# 7_1_VA_CP.net
KiCad netlist of a schematic drawn in Altium Designer
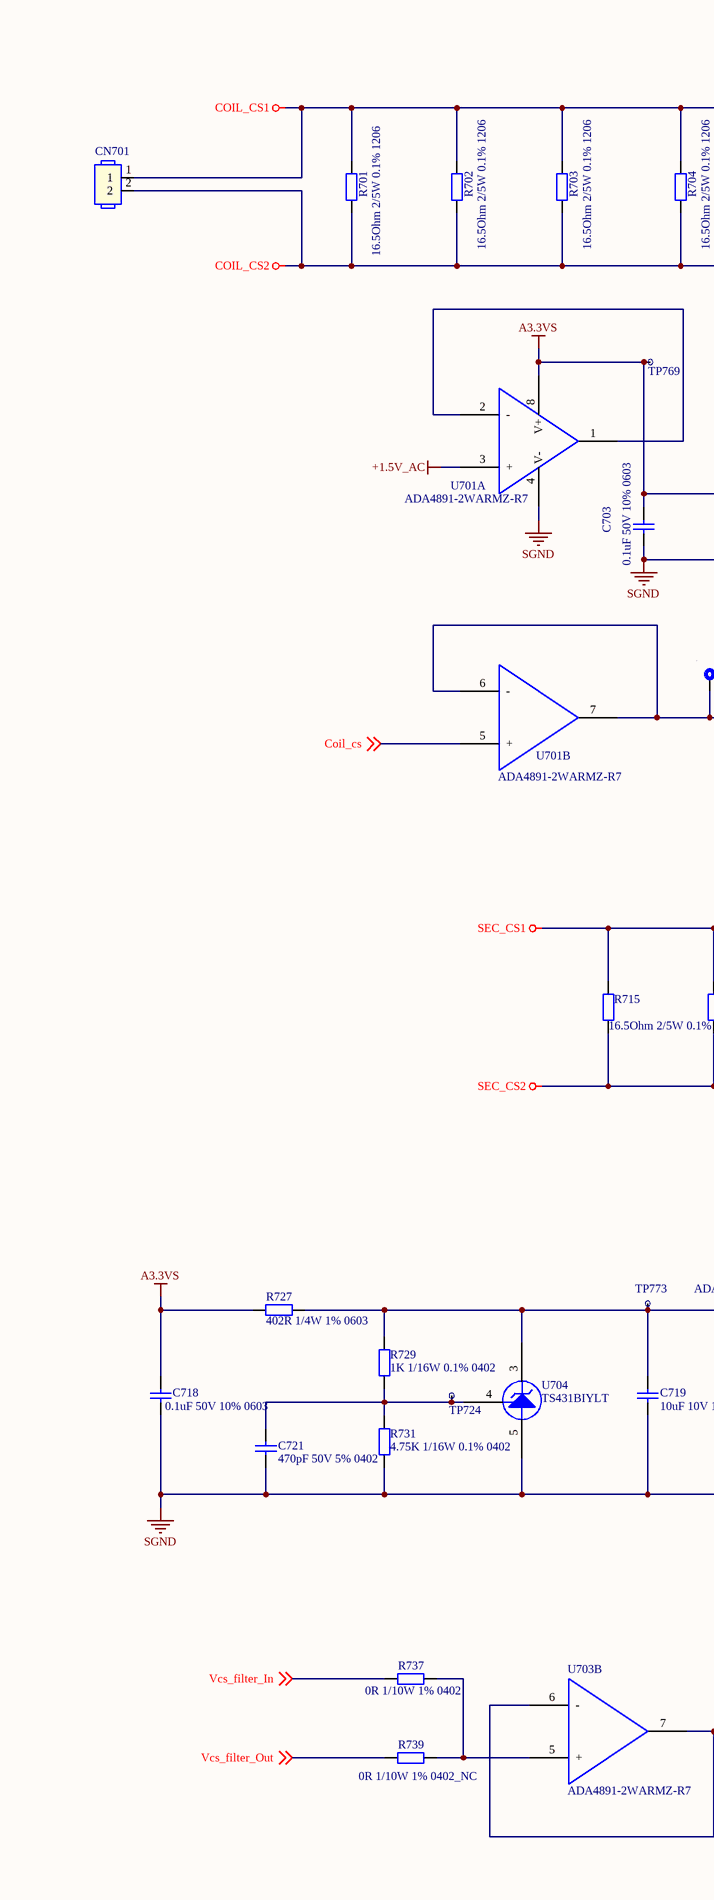
[diagram p0: 7.1 VA_CP.SchDoc, left]
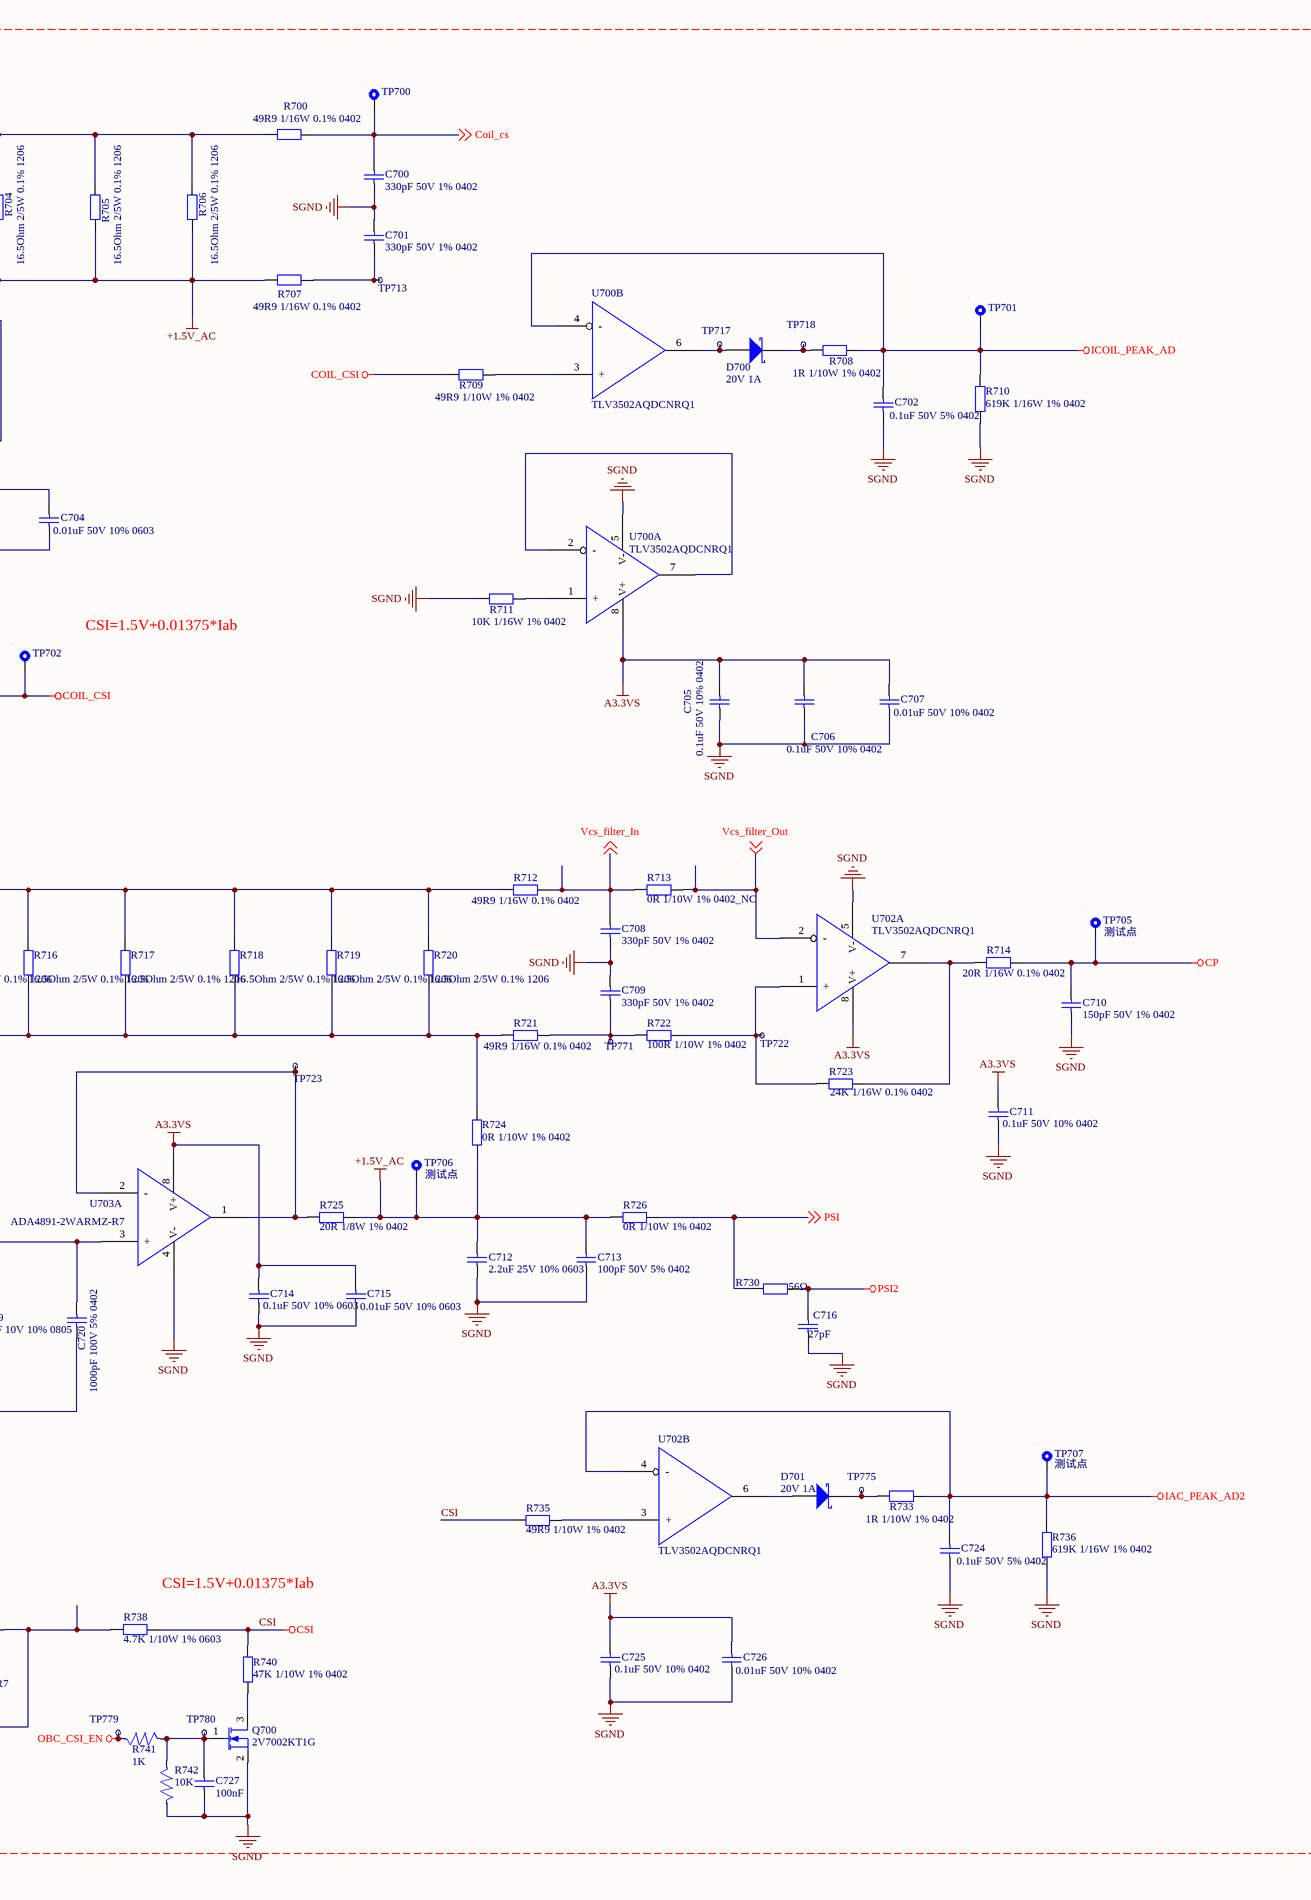
[diagram p1: 7.1 VA_CP.SchDoc, right]

(export (version "E")
  (design (tool "Eeschema 10.0.6"))
  (components
    (comp (ref "C700")
      (value "330pF 50V 1% 0402")
      (footprint "C0402")
      (description "CAP CER 330pF 50V 1% C0G/NP0 0402 AEC-Q200 SMD")
      (libsource (lib "Miscellaneous Devices") (part "Cap Semi"))
    )
    (comp (ref "C701")
      (value "330pF 50V 1% 0402")
      (footprint "C0402")
      (description "CAP CER 330pF 50V 1% C0G/NP0 0402 AEC-Q200 SMD")
      (libsource (lib "Miscellaneous Devices") (part "Cap Semi"))
    )
    (comp (ref "C702")
      (value "0.1uF 50V 5% 0402")
      (footprint "C0402")
      (description "CAP CER 0.1uF 100V 5% C0G/NP0 1206 AEC-Q200 SMD")
      (libsource (lib "Miscellaneous Devices") (part "Cap Semi"))
    )
    (comp (ref "C703")
      (value "0.1uF 50V 10% 0603")
      (footprint "C0603")
      (description "CAP CER 0.1uF 50V 10% X7R 0603 AEC-Q200 SMD")
      (libsource (lib "Miscellaneous Devices") (part "Cap Semi"))
    )
    (comp (ref "C704")
      (value "0.01uF 50V 10% 0603")
      (footprint "C0603")
      (description "CAP CER 0.01uF 50V 10% X7R 0603 AEC-Q200 SMD")
      (libsource (lib "Miscellaneous Devices") (part "Cap Semi"))
    )
    (comp (ref "C705")
      (value "0.1uF 50V 10% 0402")
      (footprint "C0402")
      (description "CAP CER 0.1uF 50V 10% X7R 0603 AEC-Q200 SMD")
      (libsource (lib "Miscellaneous Devices") (part "Cap Semi"))
    )
    (comp (ref "C706")
      (value "0.1uF 50V 10% 0402")
      (footprint "C0402")
      (description "CAP CER 0.1uF 50V 10% X7R 0603 AEC-Q200 SMD")
      (libsource (lib "Miscellaneous Devices") (part "Cap Semi"))
    )
    (comp (ref "C707")
      (value "0.01uF 50V 10% 0402")
      (footprint "C0402")
      (description "CAP CER 0.01uF 50V 10% X7R 0603 AEC-Q200 SMD")
      (libsource (lib "Miscellaneous Devices") (part "Cap Semi"))
    )
    (comp (ref "C708")
      (value "330pF 50V 1% 0402")
      (footprint "C0402")
      (description "CAP CER 330pF 50V 1% C0G/NP0 0402 AEC-Q200 SMD")
      (libsource (lib "Miscellaneous Devices") (part "Cap Semi"))
    )
    (comp (ref "C709")
      (value "330pF 50V 1% 0402")
      (footprint "C0402")
      (description "CAP CER 330pF 50V 1% C0G/NP0 0402 AEC-Q200 SMD")
      (libsource (lib "Miscellaneous Devices") (part "Cap Semi"))
    )
    (comp (ref "C710")
      (value "150pF 50V 1% 0402")
      (footprint "C0402")
      (description "CAP CER 150pF 50V 1% C0G/NP0 AEC-Q200 0402 SMD")
      (libsource (lib "Miscellaneous Devices") (part "Cap Semi"))
    )
    (comp (ref "C711")
      (value "0.1uF 50V 10% 0402")
      (footprint "C0402")
      (description "CAP CER 0.1uF 50V 10% X7R 0603 AEC-Q200 SMD")
      (libsource (lib "Miscellaneous Devices") (part "Cap Semi"))
    )
    (comp (ref "C712")
      (value "2.2uF 25V 10% 0603")
      (footprint "C0603")
      (description "CAP CER 2.2uF 25V 10% X5R 0603 SMD")
      (libsource (lib "Miscellaneous Devices") (part "Cap Semi"))
    )
    (comp (ref "C713")
      (value "100pF 50V 5% 0402")
      (footprint "C0402")
      (description "CAP CER 100pF 50V 5% C0G/NP0 0603 SMD")
      (libsource (lib "Miscellaneous Devices") (part "Cap Semi"))
    )
    (comp (ref "C714")
      (value "0.1uF 50V 10% 0603")
      (footprint "C0402")
      (description "CAP CER 0.1uF 50V 10% X7R 0603 AEC-Q200 SMD")
      (libsource (lib "Miscellaneous Devices") (part "Cap Semi"))
    )
    (comp (ref "C715")
      (value "0.01uF 50V 10% 0603")
      (footprint "C0402")
      (description "CAP CER 0.01uF 50V 10% X7R 0603 AEC-Q200 SMD")
      (libsource (lib "Miscellaneous Devices") (part "Cap Semi"))
    )
    (comp (ref "C716")
      (value "27pF 50V±5% C0G  0402")
      (footprint "C0402")
      (fields (field (name "值") "27pF"))
      (libsource (lib "贴片电容原理图封装库") (part "27pF 50V±5% C0G  0402"))
    )
    (comp (ref "C718")
      (value "0.1uF 50V 10% 0603")
      (footprint "C0603")
      (description "CAP CER 0.1uF 50V 10% X7R 0603 AEC-Q200 SMD")
      (libsource (lib "Miscellaneous Devices") (part "Cap Semi"))
    )
    (comp (ref "C719")
      (value "10uF 10V 10% 0805")
      (footprint "C0805")
      (description "CAP CER 10uF 35V 10% X5R 0805 SMD")
      (libsource (lib "Miscellaneous Devices") (part "Cap Semi"))
    )
    (comp (ref "C720")
      (value "1000pF 100V 5% 0402")
      (footprint "C0402")
      (description "CAP CER 1000pF 100V 5% X7R 0402 AEC-Q200 SMD")
      (libsource (lib "Miscellaneous Devices") (part "Cap Semi"))
    )
    (comp (ref "C721")
      (value "470pF 50V 5% 0402")
      (footprint "C0402")
      (description "CAP CER 470pF 50V 5% C0G/NP0 0402 AEC-Q200 SMD")
      (libsource (lib "Miscellaneous Devices") (part "Cap Semi"))
    )
    (comp (ref "C724")
      (value "0.1uF 50V 5% 0402")
      (footprint "C0402")
      (description "CAP CER 0.1uF 100V 5% C0G/NP0 1206 AEC-Q200 SMD")
      (libsource (lib "Miscellaneous Devices") (part "Cap Semi"))
    )
    (comp (ref "C725")
      (value "0.1uF 50V 10% 0402")
      (footprint "C0402")
      (description "CAP CER 0.1uF 50V 10% X7R 0603 AEC-Q200 SMD")
      (libsource (lib "Miscellaneous Devices") (part "Cap Semi"))
    )
    (comp (ref "C726")
      (value "0.01uF 50V 10% 0402")
      (footprint "C0402")
      (description "CAP CER 0.01uF 50V 10% X7R 0603 AEC-Q200 SMD")
      (libsource (lib "Miscellaneous Devices") (part "Cap Semi"))
    )
    (comp (ref "C727")
      (value "100nF")
      (footprint "C0402")
      (fields (field (name "MANUFACTURER") "Yageo"))
      (libsource (lib "*") (part "Cap"))
    )
    (comp (ref "CN701")
      (value "~")
      (footprint "HY_2MM_1*2P_90MOLEX01")
      (description "CN1.25-02P")
      (libsource (lib "原理图符号库2.0") (part "CN1.25-02P"))
    )
    (comp (ref "D700")
      (value "20V 1A")
      (footprint "SOD-882D")
      (description "DIODE SBD 20V 1A SOD-882D AEC-Q101")
      (libsource (lib "Miscellaneous Devices") (part "D Schottky"))
    )
    (comp (ref "D701")
      (value "20V 1A")
      (footprint "SOD-882D")
      (description "DIODE SBD 20V 1A SOD-882D AEC-Q101")
      (libsource (lib "Miscellaneous Devices") (part "D Schottky"))
    )
    (comp (ref "Q700")
      (value "2V7002KT1G")
      (footprint "Q_SOT23 - 2")
      (fields (field (name "MANUFACTURER") "ONSemi"))
      (libsource (lib "*") (part "MOSFET_N CHANNEL"))
    )
    (comp (ref "R700")
      (value "49R9 1/16W 0.1% 0402")
      (footprint "R0402")
      (description "RES Thin Film 49R9 1/16W 0.1% 0402 AEC-Q200 SMD")
      (libsource (lib "") (part "Res2_2"))
    )
    (comp (ref "R701")
      (value "16.5Ohm 2/5W 0.1% 1206")
      (footprint "R1206")
      (description "RES Thin Film 16.5Ohm 2/5W 0.1% 1206 AEC-Q200 SMD")
      (libsource (lib "") (part "Res2_1"))
    )
    (comp (ref "R702")
      (value "16.5Ohm 2/5W 0.1% 1206")
      (footprint "R1206")
      (description "RES Thin Film 16.5Ohm 2/5W 0.1% 1206 AEC-Q200 SMD")
      (libsource (lib "") (part "Res2_1"))
    )
    (comp (ref "R703")
      (value "16.5Ohm 2/5W 0.1% 1206")
      (footprint "R1206")
      (description "RES Thin Film 16.5Ohm 2/5W 0.1% 1206 AEC-Q200 SMD")
      (libsource (lib "") (part "Res2_1"))
    )
    (comp (ref "R704")
      (value "16.5Ohm 2/5W 0.1% 1206")
      (footprint "R1206")
      (description "RES Thin Film 16.5Ohm 2/5W 0.1% 1206 AEC-Q200 SMD")
      (libsource (lib "") (part "Res2_1"))
    )
    (comp (ref "R705")
      (value "16.5Ohm 2/5W 0.1% 1206")
      (footprint "R1206")
      (description "RES Thin Film 16.5Ohm 2/5W 0.1% 1206 AEC-Q200 SMD")
      (libsource (lib "") (part "Res2_1"))
    )
    (comp (ref "R706")
      (value "16.5Ohm 2/5W 0.1% 1206")
      (footprint "R1206")
      (description "RES Thin Film 16.5Ohm 2/5W 0.1% 1206 AEC-Q200 SMD")
      (libsource (lib "") (part "Res2_1"))
    )
    (comp (ref "R707")
      (value "49R9 1/16W 0.1% 0402")
      (footprint "R0402")
      (description "RES Thin Film 49R9 1/16W 0.1% 0402 AEC-Q200 SMD")
      (libsource (lib "") (part "Res2_2"))
    )
    (comp (ref "R708")
      (value "1R 1/10W 1% 0402")
      (footprint "R0402")
      (description "RES Thick Film 1R 1/10W 1% 0603 AEC-Q200 SMD")
      (libsource (lib "") (part "Res2_2"))
    )
    (comp (ref "R709")
      (value "49R9 1/10W 1% 0402")
      (footprint "R0402")
      (description "RES Thick Film 49R9 1/10W 1% 0603 AEC-Q200 SMD")
      (libsource (lib "") (part "Res2_2"))
    )
    (comp (ref "R710")
      (value "619K 1/16W 1% 0402")
      (footprint "R0402")
      (description "RES Thick Film 619K 1/16W 1% 0402 AEC-Q200 SMD")
      (libsource (lib "Miscellaneous Devices") (part "Res2"))
    )
    (comp (ref "R711")
      (value "10K 1/16W 1% 0402")
      (footprint "R0402")
      (description "RES Thick Film 10K 1/16W 1% 0402 SMD")
      (libsource (lib "") (part "Res2_2"))
    )
    (comp (ref "R712")
      (value "49R9 1/16W 0.1% 0402")
      (footprint "R0402")
      (description "RES Thin Film 49R9 1/16W 0.1% 0402 AEC-Q200 SMD")
      (libsource (lib "") (part "Res2_2"))
    )
    (comp (ref "R713")
      (value "0R 1/10W 1% 0402_NC")
      (footprint "R0402")
      (description "RES Thick Film 0R 1/10W 1% 0603 SMD")
      (libsource (lib "") (part "Res2_2"))
    )
    (comp (ref "R714")
      (value "20R 1/16W 0.1% 0402")
      (footprint "R0402")
      (description "RES Thin Film 20R 1/16W 0.1% 0402 AEC-Q200 SMD")
      (libsource (lib "") (part "Res2_2"))
    )
    (comp (ref "R715")
      (value "16.5Ohm 2/5W 0.1% 1206")
      (footprint "R1206")
      (description "RES Thin Film 16.5Ohm 2/5W 0.1% 1206 AEC-Q200 SMD")
      (libsource (lib "") (part "Res2_1"))
    )
    (comp (ref "R716")
      (value "16.5Ohm 2/5W 0.1% 1206")
      (footprint "R1206")
      (description "RES Thin Film 16.5Ohm 2/5W 0.1% 1206 AEC-Q200 SMD")
      (libsource (lib "") (part "Res2_1"))
    )
    (comp (ref "R717")
      (value "16.5Ohm 2/5W 0.1% 1206")
      (footprint "R1206")
      (description "RES Thin Film 16.5Ohm 2/5W 0.1% 1206 AEC-Q200 SMD")
      (libsource (lib "") (part "Res2_1"))
    )
    (comp (ref "R718")
      (value "16.5Ohm 2/5W 0.1% 1206")
      (footprint "R1206")
      (description "RES Thin Film 16.5Ohm 2/5W 0.1% 1206 AEC-Q200 SMD")
      (libsource (lib "") (part "Res2_1"))
    )
    (comp (ref "R719")
      (value "16.5Ohm 2/5W 0.1% 1206")
      (footprint "R1206")
      (description "RES Thin Film 16.5Ohm 2/5W 0.1% 1206 AEC-Q200 SMD")
      (libsource (lib "") (part "Res2_1"))
    )
    (comp (ref "R720")
      (value "16.5Ohm 2/5W 0.1% 1206")
      (footprint "R1206")
      (description "RES Thin Film 16.5Ohm 2/5W 0.1% 1206 AEC-Q200 SMD")
      (libsource (lib "") (part "Res2_1"))
    )
    (comp (ref "R721")
      (value "49R9 1/16W 0.1% 0402")
      (footprint "R0402")
      (description "RES Thin Film 49R9 1/16W 0.1% 0402 AEC-Q200 SMD")
      (libsource (lib "") (part "Res2_2"))
    )
    (comp (ref "R722")
      (value "100R 1/10W 1% 0402")
      (footprint "R0402")
      (description "RES Thick Film 100R 1/10W 1% 0603 AEC-Q200 SMD")
      (libsource (lib "") (part "Res2_2"))
    )
    (comp (ref "R723")
      (value "24K 1/16W 0.1% 0402")
      (footprint "R0402")
      (description "RES Thin Film 24K 1/16W 0.1% 0402 AEC-Q200 SMD")
      (libsource (lib "") (part "Res2_2"))
    )
    (comp (ref "R724")
      (value "0R 1/10W 1% 0402")
      (footprint "R0402")
      (description "RES Thick Film 0R 1/10W 1% AEC-Q200 0603 SMD")
      (libsource (lib "Miscellaneous Devices") (part "Res2"))
    )
    (comp (ref "R725")
      (value "20R 1/8W 1% 0402")
      (footprint "R0402")
      (description "RES Thick Film 20R 1/8W 1% 0805 AEC-Q200 SMD")
      (libsource (lib "") (part "Res2_2"))
    )
    (comp (ref "R726")
      (value "0R 1/10W 1% 0402")
      (footprint "R0402")
      (description "RES Thick Film 0R 1/10W 1% AEC-Q200 0603 SMD")
      (libsource (lib "") (part "Res2_2"))
    )
    (comp (ref "R727")
      (value "402R 1/4W 1% 0603")
      (footprint "R0603")
      (description "RES Thick Film 402R 1/4W 1% 1206 AEC-Q200 SMD")
      (libsource (lib "") (part "Res2_2"))
    )
    (comp (ref "R729")
      (value "1K 1/16W 0.1% 0402")
      (footprint "R0402")
      (description "RES Thin Film 1K 1/16W 0.1% 0402 AEC-Q200 SMD")
      (libsource (lib "") (part "Res2_1"))
    )
    (comp (ref "R730")
      (value "56Ω ±1% 1/16W 0402")
      (footprint "R0402")
      (fields (field (name "值") "56Ω"))
      (libsource (lib "贴片电阻原理图封装库") (part "56Ω ±1% 1/16W 0402"))
    )
    (comp (ref "R731")
      (value "4.75K 1/16W 0.1% 0402")
      (footprint "R0402")
      (description "RES Thin Film 4.75K 1/16W 0.1% 0402 AEC-Q200 SMD")
      (libsource (lib "") (part "Res2_1"))
    )
    (comp (ref "R733")
      (value "1R 1/10W 1% 0402")
      (footprint "R0402")
      (description "RES Thick Film 1R 1/10W 1% 0603 AEC-Q200 SMD")
      (libsource (lib "") (part "Res2_2"))
    )
    (comp (ref "R735")
      (value "49R9 1/10W 1% 0402")
      (footprint "R0402")
      (description "RES Thick Film 49R9 1/10W 1% 0603 AEC-Q200 SMD")
      (libsource (lib "") (part "Res2_2"))
    )
    (comp (ref "R736")
      (value "619K 1/16W 1% 0402")
      (footprint "R0402")
      (description "RES Thick Film 619K 1/16W 1% 0402 AEC-Q200 SMD")
      (libsource (lib "Miscellaneous Devices") (part "Res2"))
    )
    (comp (ref "R737")
      (value "0R 1/10W 1% 0402")
      (footprint "R0402")
      (description "RES Thick Film 0R 1/10W 1% AEC-Q200 0603 SMD")
      (libsource (lib "") (part "Res2_2"))
    )
    (comp (ref "R738")
      (value "4.7K 1/10W 1% 0603")
      (footprint "R0402")
      (description "RES Thick Film 49R9 1/10W 1% 0603 AEC-Q200 SMD")
      (libsource (lib "") (part "Res2_2"))
    )
    (comp (ref "R739")
      (value "0R 1/10W 1% 0402_NC")
      (footprint "R0402")
      (description "RES Thick Film 0R 1/10W 1% AEC-Q200 0603 SMD")
      (libsource (lib "") (part "Res2_2"))
    )
    (comp (ref "R740")
      (value "47K 1/10W 1% 0402")
      (footprint "R0402")
      (description "RES Thick Film 49R9 1/10W 1% 0603 AEC-Q200 SMD")
      (libsource (lib "Miscellaneous Devices") (part "Res2"))
    )
    (comp (ref "R741")
      (value "1K")
      (footprint "R0402")
      (fields (field (name "MANUFACTURER") "Yageo"))
      (libsource (lib "*") (part "RESISTOR_1206"))
    )
    (comp (ref "R742")
      (value "10K")
      (footprint "R0402")
      (fields (field (name "MANUFACTURER") "Yageo"))
      (libsource (lib "*") (part "RESISTOR_1206"))
    )
    (comp (ref "TP700")
      (value "测试点")
      (footprint "测试点")
      (description "Test Point 1mm")
      (libsource (lib "Test Point") (part "Test Point"))
    )
    (comp (ref "TP701")
      (value "测试点")
      (footprint "测试点")
      (description "Test Point 1mm")
      (libsource (lib "Test Point") (part "Test Point"))
    )
    (comp (ref "TP702")
      (value "测试点")
      (footprint "测试点")
      (description "Test Point 1mm")
      (libsource (lib "Test Point") (part "Test Point"))
    )
    (comp (ref "TP705")
      (value "测试点")
      (footprint "测试点")
      (description "Test Point 1mm")
      (libsource (lib "Test Point") (part "Test Point"))
    )
    (comp (ref "TP706")
      (value "测试点")
      (footprint "测试点")
      (description "Test Point 1mm")
      (libsource (lib "Test Point") (part "Test Point"))
    )
    (comp (ref "TP707")
      (value "测试点")
      (footprint "测试点")
      (description "Test Point 1mm")
      (libsource (lib "Test Point") (part "Test Point"))
    )
    (comp (ref "TP713") (value "测试点") (footprint "测试点") (libsource (lib "原理图符号库2.0") (part "测试点")))
    (comp (ref "TP717") (value "测试点") (footprint "测试点") (libsource (lib "原理图符号库2.0") (part "测试点")))
    (comp (ref "TP718") (value "测试点") (footprint "测试点") (libsource (lib "原理图符号库2.0") (part "测试点")))
    (comp (ref "TP722") (value "测试点") (footprint "测试点") (libsource (lib "原理图符号库2.0") (part "测试点")))
    (comp (ref "TP723") (value "测试点") (footprint "测试点") (libsource (lib "原理图符号库2.0") (part "测试点")))
    (comp (ref "TP724") (value "测试点") (footprint "测试点") (libsource (lib "原理图符号库2.0") (part "测试点")))
    (comp (ref "TP769") (value "测试点") (footprint "测试点") (libsource (lib "原理图符号库2.0") (part "测试点")))
    (comp (ref "TP771") (value "测试点") (footprint "测试点") (libsource (lib "原理图符号库2.0") (part "测试点")))
    (comp (ref "TP773") (value "测试点") (footprint "测试点") (libsource (lib "原理图符号库2.0") (part "测试点")))
    (comp (ref "TP775") (value "测试点") (footprint "测试点") (libsource (lib "原理图符号库2.0") (part "测试点")))
    (comp (ref "TP779") (value "测试点") (footprint "测试点") (libsource (lib "原理图符号库2.0") (part "测试点")))
    (comp (ref "TP780") (value "测试点") (footprint "测试点") (libsource (lib "原理图符号库2.0") (part "测试点")))
    (comp (ref "U700")
      (value "TLV3502AQDCNRQ1")
      (footprint "SON-8")
      (description "IC COMPARATOR 2.7V~5.5V SOT23-8")
      (libsource (lib "TLV3502AQDCNRQ1") (part "TLV3502AQDCNRQ1"))
    )
    (comp (ref "U701")
      (value "ADA4891-2WARMZ-R7")
      (footprint "SOIC_8")
      (description "IC, High Speed, Rail-to-Rail Amplifiers, 2.7V~5.5V, MSOP-8")
      (libsource (lib "ADA4891-2WARMZ-R7") (part "ADA4891-2WARMZ-R7"))
    )
    (comp (ref "U702")
      (value "TLV3502AQDCNRQ1")
      (footprint "SON-8")
      (description "IC COMPARATOR 2.7V~5.5V SOT23-8")
      (libsource (lib "TLV3502AQDCNRQ1") (part "TLV3502AQDCNRQ1"))
    )
    (comp (ref "U703")
      (value "ADA4891-2WARMZ-R7")
      (footprint "SOIC_8")
      (description "IC, High Speed, Rail-to-Rail Amplifiers, 2.7V~5.5V, MSOP-8")
      (libsource (lib "ADA4891-2WARMZ-R7") (part "ADA4891-2WARMZ-R7"))
    )
    (comp (ref "U704")
      (value "TS431BIYLT")
      (footprint "SOT23-5")
      (description "IC VREF SHUNT ADJ 1.24V~6V 30mA SOT23-5")
      (libsource (lib "TS431BIYLT") (part "TS431BIYLT"))
    )
  )
  (nets
    (net (code "1") (name "+1.5V_AC") (class "Default")
      (node (ref "C712") (pin "2") (pinfunction "2_2") (pintype "passive"))
      (node (ref "C713") (pin "2") (pinfunction "2_2") (pintype "passive"))
      (node (ref "CN701") (pin "2") (pinfunction "2_2") (pintype "passive"))
      (node (ref "R701") (pin "1") (pinfunction "1_1") (pintype "passive"))
      (node (ref "R702") (pin "1") (pinfunction "1_1") (pintype "passive"))
      (node (ref "R703") (pin "1") (pinfunction "1_1") (pintype "passive"))
      (node (ref "R704") (pin "1") (pinfunction "1_1") (pintype "passive"))
      (node (ref "R705") (pin "1") (pinfunction "1_1") (pintype "passive"))
      (node (ref "R706") (pin "1") (pinfunction "1_1") (pintype "passive"))
      (node (ref "R707") (pin "2") (pinfunction "2_2") (pintype "passive"))
      (node (ref "R724") (pin "2") (pinfunction "2_2") (pintype "passive"))
      (node (ref "R725") (pin "1") (pinfunction "1_1") (pintype "passive"))
      (node (ref "R726") (pin "2") (pinfunction "2_2") (pintype "passive"))
      (node (ref "TP706") (pin "1") (pintype "passive"))
      (node (ref "U701") (pin "3") (pinfunction "+_3") (pintype "passive"))
    )
    (net (code "2") (name "A3.3VS") (class "Default")
      (node (ref "C703") (pin "1") (pinfunction "1_1") (pintype "passive"))
      (node (ref "C704") (pin "1") (pinfunction "1_1") (pintype "passive"))
      (node (ref "C705") (pin "1") (pinfunction "1_1") (pintype "passive"))
      (node (ref "C706") (pin "1") (pinfunction "1_1") (pintype "passive"))
      (node (ref "C707") (pin "1") (pinfunction "1_1") (pintype "passive"))
      (node (ref "C711") (pin "1") (pinfunction "1_1") (pintype "passive"))
      (node (ref "C714") (pin "1") (pinfunction "1_1") (pintype "passive"))
      (node (ref "C715") (pin "1") (pinfunction "1_1") (pintype "passive"))
      (node (ref "C718") (pin "1") (pinfunction "1_1") (pintype "passive"))
      (node (ref "C725") (pin "1") (pinfunction "1_1") (pintype "passive"))
      (node (ref "C726") (pin "1") (pinfunction "1_1") (pintype "passive"))
      (node (ref "R727") (pin "2") (pinfunction "2_2") (pintype "passive"))
      (node (ref "TP769") (pin "1") (pinfunction "1_1") (pintype "passive"))
      (node (ref "U700") (pin "8") (pinfunction "V+_8") (pintype "passive"))
      (node (ref "U701") (pin "8") (pinfunction "V+_8") (pintype "passive"))
      (node (ref "U702") (pin "8") (pinfunction "V+_8") (pintype "passive"))
      (node (ref "U703") (pin "8") (pinfunction "V+_8") (pintype "passive"))
    )
    (net (code "3") (name "COIL_CS1") (class "Default")
      (node (ref "CN701") (pin "1") (pinfunction "1_1") (pintype "passive"))
      (node (ref "R700") (pin "2") (pinfunction "2_2") (pintype "passive"))
      (node (ref "R701") (pin "2") (pinfunction "2_2") (pintype "passive"))
      (node (ref "R702") (pin "2") (pinfunction "2_2") (pintype "passive"))
      (node (ref "R703") (pin "2") (pinfunction "2_2") (pintype "passive"))
      (node (ref "R704") (pin "2") (pinfunction "2_2") (pintype "passive"))
      (node (ref "R705") (pin "2") (pinfunction "2_2") (pintype "passive"))
      (node (ref "R706") (pin "2") (pinfunction "2_2") (pintype "passive"))
    )
    (net (code "4") (name "COIL_CSI") (class "Default")
      (node (ref "R709") (pin "2") (pinfunction "2_2") (pintype "passive"))
      (node (ref "TP702") (pin "1") (pintype "passive"))
      (node (ref "U701") (pin "6") (pinfunction "-_6") (pintype "passive"))
      (node (ref "U701") (pin "7") (pintype "passive"))
    )
    (net (code "5") (name "CP") (class "Default")
      (node (ref "C710") (pin "2") (pinfunction "2_2") (pintype "passive"))
      (node (ref "R714") (pin "1") (pinfunction "1_1") (pintype "passive"))
      (node (ref "TP705") (pin "1") (pintype "passive"))
    )
    (net (code "6") (name "CSI") (class "Default")
      (node (ref "R735") (pin "2") (pinfunction "2_2") (pintype "passive"))
      (node (ref "R738") (pin "1") (pinfunction "1_1") (pintype "passive"))
      (node (ref "R740") (pin "1") (pinfunction "1_1") (pintype "passive"))
    )
    (net (code "7") (name "Coil_cs") (class "Default")
      (node (ref "C700") (pin "2") (pinfunction "2_2") (pintype "passive"))
      (node (ref "R700") (pin "1") (pinfunction "1_1") (pintype "passive"))
      (node (ref "TP700") (pin "1") (pintype "passive"))
      (node (ref "U701") (pin "5") (pinfunction "+_5") (pintype "passive"))
    )
    (net (code "8") (name "IAC_PEAK_AD2") (class "Default")
      (node (ref "C724") (pin "2") (pinfunction "2_2") (pintype "passive"))
      (node (ref "R733") (pin "1") (pinfunction "1_1") (pintype "passive"))
      (node (ref "R736") (pin "1") (pinfunction "1_1") (pintype "passive"))
      (node (ref "TP707") (pin "1") (pintype "passive"))
      (node (ref "U702") (pin "4") (pinfunction "-_4") (pintype "passive"))
    )
    (net (code "9") (name "ICOIL_PEAK_AD") (class "Default")
      (node (ref "C702") (pin "2") (pinfunction "2_2") (pintype "passive"))
      (node (ref "R708") (pin "1") (pinfunction "1_1") (pintype "passive"))
      (node (ref "R710") (pin "1") (pinfunction "1_1") (pintype "passive"))
      (node (ref "TP701") (pin "1") (pintype "passive"))
      (node (ref "U700") (pin "4") (pinfunction "-_4") (pintype "passive"))
    )
    (net (code "10") (name "Net-(C701-Pad1)") (class "Default")
      (node (ref "C701") (pin "1") (pinfunction "1_1") (pintype "passive"))
      (node (ref "R707") (pin "1") (pinfunction "1_1") (pintype "passive"))
      (node (ref "TP713") (pin "1") (pinfunction "1_1") (pintype "passive"))
    )
    (net (code "11") (name "Net-(C709-Pad1)") (class "Default")
      (node (ref "C709") (pin "1") (pinfunction "1_1") (pintype "passive"))
      (node (ref "R721") (pin "1") (pinfunction "1_1") (pintype "passive"))
      (node (ref "R722") (pin "2") (pinfunction "2_2") (pintype "passive"))
      (node (ref "TP771") (pin "1") (pinfunction "1_1") (pintype "passive"))
    )
    (net (code "12") (name "Net-(C721-Pad2)") (class "Default")
      (node (ref "C721") (pin "2") (pinfunction "2_2") (pintype "passive"))
      (node (ref "R729") (pin "1") (pinfunction "1_1") (pintype "passive"))
      (node (ref "R731") (pin "2") (pinfunction "2_2") (pintype "passive"))
      (node (ref "TP724") (pin "1") (pinfunction "1_1") (pintype "passive"))
      (node (ref "U704") (pin "4") (pintype "passive"))
    )
    (net (code "13") (name "Net-(D700-A)") (class "Default")
      (node (ref "D700") (pin "1") (pinfunction "A_1") (pintype "passive"))
      (node (ref "TP717") (pin "1") (pinfunction "1_1") (pintype "passive"))
      (node (ref "U700") (pin "6") (pintype "passive"))
    )
    (net (code "14") (name "Net-(D700-K)") (class "Default")
      (node (ref "D700") (pin "2") (pinfunction "K_2") (pintype "passive"))
      (node (ref "R708") (pin "2") (pinfunction "2_2") (pintype "passive"))
      (node (ref "TP718") (pin "1") (pinfunction "1_1") (pintype "passive"))
    )
    (net (code "15") (name "Net-(D701-A)") (class "Default")
      (node (ref "D701") (pin "1") (pinfunction "A_1") (pintype "passive"))
      (node (ref "U702") (pin "6") (pintype "passive"))
    )
    (net (code "16") (name "Net-(D701-K)") (class "Default")
      (node (ref "D701") (pin "2") (pinfunction "K_2") (pintype "passive"))
      (node (ref "R733") (pin "2") (pinfunction "2_2") (pintype "passive"))
      (node (ref "TP775") (pin "1") (pinfunction "1_1") (pintype "passive"))
    )
    (net (code "17") (name "Net-(Q700-D)") (class "Default")
      (node (ref "Q700") (pin "3") (pinfunction "D_3") (pintype "passive"))
      (node (ref "R740") (pin "2") (pinfunction "2_2") (pintype "passive"))
    )
    (net (code "18") (name "Net-(Q700-G)") (class "Default")
      (node (ref "C727") (pin "1") (pinfunction "1_1") (pintype "passive"))
      (node (ref "Q700") (pin "1") (pinfunction "G_1") (pintype "passive"))
      (node (ref "R741") (pin "1") (pinfunction "1_1") (pintype "passive"))
      (node (ref "R742") (pin "1") (pinfunction "1_1") (pintype "passive"))
      (node (ref "TP780") (pin "1") (pinfunction "1_1") (pintype "passive"))
    )
    (net (code "19") (name "Net-(R714-Pad2)") (class "Default")
      (node (ref "R714") (pin "2") (pinfunction "2_2") (pintype "passive"))
      (node (ref "R723") (pin "1") (pinfunction "1_1") (pintype "passive"))
      (node (ref "U702") (pin "7") (pintype "passive"))
    )
    (net (code "20") (name "Net-(U700A-+)") (class "Default")
      (node (ref "R711") (pin "1") (pinfunction "1_1") (pintype "passive"))
      (node (ref "U700") (pin "1") (pinfunction "+_1") (pintype "passive"))
    )
    (net (code "21") (name "Net-(U700A--)") (class "Default")
      (node (ref "U700") (pin "2") (pinfunction "-_2") (pintype "passive"))
      (node (ref "U700") (pin "7") (pintype "passive"))
    )
    (net (code "22") (name "Net-(U700B-+)") (class "Default")
      (node (ref "R709") (pin "1") (pinfunction "1_1") (pintype "passive"))
      (node (ref "U700") (pin "3") (pinfunction "+_3") (pintype "passive"))
    )
    (net (code "23") (name "Net-(U701A--)") (class "Default")
      (node (ref "U701") (pin "1") (pintype "passive"))
      (node (ref "U701") (pin "2") (pinfunction "-_2") (pintype "passive"))
    )
    (net (code "24") (name "Net-(U702A-+)") (class "Default")
      (node (ref "R722") (pin "1") (pinfunction "1_1") (pintype "passive"))
      (node (ref "R723") (pin "2") (pinfunction "2_2") (pintype "passive"))
      (node (ref "TP722") (pin "1") (pinfunction "1_1") (pintype "passive"))
      (node (ref "U702") (pin "1") (pinfunction "+_1") (pintype "passive"))
    )
    (net (code "25") (name "Net-(U702B-+)") (class "Default")
      (node (ref "R735") (pin "1") (pinfunction "1_1") (pintype "passive"))
      (node (ref "U702") (pin "3") (pinfunction "+_3") (pintype "passive"))
    )
    (net (code "26") (name "Net-(U703A-+)") (class "Default")
      (node (ref "C719") (pin "2") (pinfunction "2_2") (pintype "passive"))
      (node (ref "C720") (pin "2") (pinfunction "2_2") (pintype "passive"))
      (node (ref "R727") (pin "1") (pinfunction "1_1") (pintype "passive"))
      (node (ref "R729") (pin "2") (pinfunction "2_2") (pintype "passive"))
      (node (ref "TP773") (pin "1") (pinfunction "1_1") (pintype "passive"))
      (node (ref "U703") (pin "3") (pinfunction "+_3") (pintype "passive"))
      (node (ref "U704") (pin "3") (pintype "passive"))
    )
    (net (code "27") (name "Net-(U703A--)") (class "Default")
      (node (ref "R725") (pin "2") (pinfunction "2_2") (pintype "passive"))
      (node (ref "TP723") (pin "1") (pinfunction "1_1") (pintype "passive"))
      (node (ref "U703") (pin "1") (pintype "passive"))
      (node (ref "U703") (pin "2") (pinfunction "-_2") (pintype "passive"))
    )
    (net (code "28") (name "Net-(U703B-+)") (class "Default")
      (node (ref "R737") (pin "1") (pinfunction "1_1") (pintype "passive"))
      (node (ref "R739") (pin "1") (pinfunction "1_1") (pintype "passive"))
      (node (ref "U703") (pin "5") (pinfunction "+_5") (pintype "passive"))
    )
    (net (code "29") (name "Net-(U703B--)") (class "Default")
      (node (ref "R738") (pin "2") (pinfunction "2_2") (pintype "passive"))
      (node (ref "U703") (pin "6") (pinfunction "-_6") (pintype "passive"))
      (node (ref "U703") (pin "7") (pintype "passive"))
    )
    (net (code "30") (name "OBC_CSI_EN") (class "Default")
      (node (ref "R741") (pin "2") (pinfunction "2_2") (pintype "passive"))
      (node (ref "TP779") (pin "1") (pinfunction "1_1") (pintype "passive"))
    )
    (net (code "31") (name "PSI") (class "Default")
      (node (ref "R726") (pin "1") (pinfunction "1_1") (pintype "passive"))
      (node (ref "R730") (pin "1") (pinfunction "1_1") (pintype "passive"))
    )
    (net (code "32") (name "PSI2") (class "Default")
      (node (ref "C716") (pin "1") (pinfunction "1_1") (pintype "passive"))
      (node (ref "R730") (pin "2") (pinfunction "2_2") (pintype "passive"))
    )
    (net (code "33") (name "SEC_CS1") (class "Default")
      (node (ref "R712") (pin "2") (pinfunction "2_2") (pintype "passive"))
      (node (ref "R715") (pin "2") (pinfunction "2_2") (pintype "passive"))
      (node (ref "R716") (pin "2") (pinfunction "2_2") (pintype "passive"))
      (node (ref "R717") (pin "2") (pinfunction "2_2") (pintype "passive"))
      (node (ref "R718") (pin "2") (pinfunction "2_2") (pintype "passive"))
      (node (ref "R719") (pin "2") (pinfunction "2_2") (pintype "passive"))
      (node (ref "R720") (pin "2") (pinfunction "2_2") (pintype "passive"))
    )
    (net (code "34") (name "SEC_CS2") (class "Default")
      (node (ref "R715") (pin "1") (pinfunction "1_1") (pintype "passive"))
      (node (ref "R716") (pin "1") (pinfunction "1_1") (pintype "passive"))
      (node (ref "R717") (pin "1") (pinfunction "1_1") (pintype "passive"))
      (node (ref "R718") (pin "1") (pinfunction "1_1") (pintype "passive"))
      (node (ref "R719") (pin "1") (pinfunction "1_1") (pintype "passive"))
      (node (ref "R720") (pin "1") (pinfunction "1_1") (pintype "passive"))
      (node (ref "R721") (pin "2") (pinfunction "2_2") (pintype "passive"))
      (node (ref "R724") (pin "1") (pinfunction "1_1") (pintype "passive"))
    )
    (net (code "35") (name "SGND") (class "Default")
      (node (ref "C700") (pin "1") (pinfunction "1_1") (pintype "passive"))
      (node (ref "C701") (pin "2") (pinfunction "2_2") (pintype "passive"))
      (node (ref "C702") (pin "1") (pinfunction "1_1") (pintype "passive"))
      (node (ref "C703") (pin "2") (pinfunction "2_2") (pintype "passive"))
      (node (ref "C704") (pin "2") (pinfunction "2_2") (pintype "passive"))
      (node (ref "C705") (pin "2") (pinfunction "2_2") (pintype "passive"))
      (node (ref "C706") (pin "2") (pinfunction "2_2") (pintype "passive"))
      (node (ref "C707") (pin "2") (pinfunction "2_2") (pintype "passive"))
      (node (ref "C708") (pin "1") (pinfunction "1_1") (pintype "passive"))
      (node (ref "C709") (pin "2") (pinfunction "2_2") (pintype "passive"))
      (node (ref "C710") (pin "1") (pinfunction "1_1") (pintype "passive"))
      (node (ref "C711") (pin "2") (pinfunction "2_2") (pintype "passive"))
      (node (ref "C712") (pin "1") (pinfunction "1_1") (pintype "passive"))
      (node (ref "C713") (pin "1") (pinfunction "1_1") (pintype "passive"))
      (node (ref "C714") (pin "2") (pinfunction "2_2") (pintype "passive"))
      (node (ref "C715") (pin "2") (pinfunction "2_2") (pintype "passive"))
      (node (ref "C716") (pin "2") (pinfunction "2_2") (pintype "passive"))
      (node (ref "C718") (pin "2") (pinfunction "2_2") (pintype "passive"))
      (node (ref "C719") (pin "1") (pinfunction "1_1") (pintype "passive"))
      (node (ref "C720") (pin "1") (pinfunction "1_1") (pintype "passive"))
      (node (ref "C721") (pin "1") (pinfunction "1_1") (pintype "passive"))
      (node (ref "C724") (pin "1") (pinfunction "1_1") (pintype "passive"))
      (node (ref "C725") (pin "2") (pinfunction "2_2") (pintype "passive"))
      (node (ref "C726") (pin "2") (pinfunction "2_2") (pintype "passive"))
      (node (ref "C727") (pin "2") (pinfunction "2_2") (pintype "passive"))
      (node (ref "Q700") (pin "2") (pinfunction "S_2") (pintype "passive"))
      (node (ref "R710") (pin "2") (pinfunction "2_2") (pintype "passive"))
      (node (ref "R711") (pin "2") (pinfunction "2_2") (pintype "passive"))
      (node (ref "R731") (pin "1") (pinfunction "1_1") (pintype "passive"))
      (node (ref "R736") (pin "2") (pinfunction "2_2") (pintype "passive"))
      (node (ref "R742") (pin "2") (pinfunction "2_2") (pintype "passive"))
      (node (ref "U700") (pin "5") (pinfunction "V-_5") (pintype "passive"))
      (node (ref "U701") (pin "4") (pinfunction "V-_4") (pintype "passive"))
      (node (ref "U702") (pin "5") (pinfunction "V-_5") (pintype "passive"))
      (node (ref "U703") (pin "4") (pinfunction "V-_4") (pintype "passive"))
      (node (ref "U704") (pin "5") (pintype "passive"))
    )
    (net (code "36") (name "Vcs_filter_In") (class "Default")
      (node (ref "C708") (pin "2") (pinfunction "2_2") (pintype "passive"))
      (node (ref "R712") (pin "1") (pinfunction "1_1") (pintype "passive"))
      (node (ref "R713") (pin "2") (pinfunction "2_2") (pintype "passive"))
      (node (ref "R737") (pin "2") (pinfunction "2_2") (pintype "passive"))
    )
    (net (code "37") (name "Vcs_filter_Out") (class "Default")
      (node (ref "R713") (pin "1") (pinfunction "1_1") (pintype "passive"))
      (node (ref "R739") (pin "2") (pinfunction "2_2") (pintype "passive"))
      (node (ref "U702") (pin "2") (pinfunction "-_2") (pintype "passive"))
    )
  )
)
